# DragonflyteConnector.net
KiCad netlist of a schematic drawn in Altium Designer
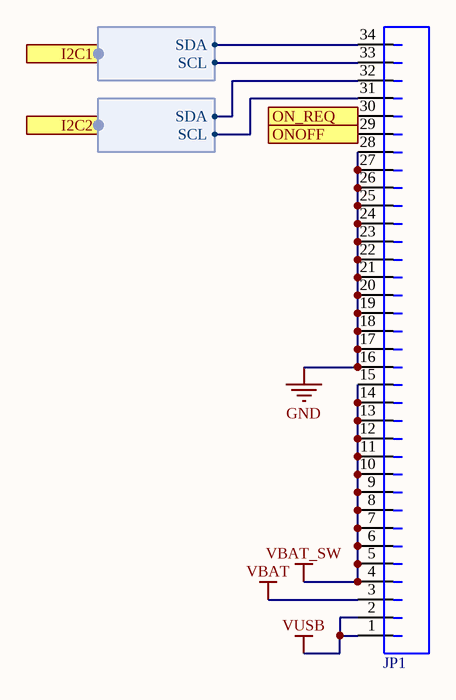
[diagram p0: DragonflyteConnector.SchDoc]

(export (version "E")
  (design (tool "Eeschema 10.0.6"))
  (components
    (comp (ref "JP1")
      (value "MOLEX_FFC-FPC_34")
      (footprint "MOLEX-FFC-FPC-0.5MM-34")
      (fields (field (name "MANUFACTURER") "Molex") (field (name "PARTNUMBER") "51296-3494"))
      (libsource (lib "Connectors") (part "MOLEX_FFC-FPC_34"))
    )
  )
  (nets
    (net (code "2") (name "/ONOFF") (class "Default")
      (node (ref "JP1") (pin "29") (pinfunction "29_29") (pintype "passive"))
    )
    (net (code "3") (name "/ON_REQ") (class "Default")
      (node (ref "JP1") (pin "30") (pinfunction "30_30") (pintype "passive"))
    )
    (net (code "5") (name "GND") (class "Default")
      (node (ref "JP1") (pin "16") (pinfunction "16_16") (pintype "passive"))
      (node (ref "JP1") (pin "17") (pinfunction "17_17") (pintype "passive"))
      (node (ref "JP1") (pin "18") (pinfunction "18_18") (pintype "passive"))
      (node (ref "JP1") (pin "19") (pinfunction "19_19") (pintype "passive"))
      (node (ref "JP1") (pin "20") (pinfunction "20_20") (pintype "passive"))
      (node (ref "JP1") (pin "21") (pinfunction "21_21") (pintype "passive"))
      (node (ref "JP1") (pin "22") (pinfunction "22_22") (pintype "passive"))
      (node (ref "JP1") (pin "23") (pinfunction "23_23") (pintype "passive"))
      (node (ref "JP1") (pin "24") (pinfunction "24_24") (pintype "passive"))
      (node (ref "JP1") (pin "25") (pinfunction "25_25") (pintype "passive"))
      (node (ref "JP1") (pin "26") (pinfunction "26_26") (pintype "passive"))
      (node (ref "JP1") (pin "27") (pinfunction "27_27") (pintype "passive"))
      (node (ref "JP1") (pin "28") (pinfunction "28_28") (pintype "passive"))
    )
    (net (code "6") (name "VBAT") (class "Default")
      (node (ref "JP1") (pin "3") (pinfunction "3_3") (pintype "passive"))
    )
    (net (code "7") (name "VBAT_SW") (class "Default")
      (node (ref "JP1") (pin "10") (pinfunction "10_10") (pintype "passive"))
      (node (ref "JP1") (pin "11") (pinfunction "11_11") (pintype "passive"))
      (node (ref "JP1") (pin "12") (pinfunction "12_12") (pintype "passive"))
      (node (ref "JP1") (pin "13") (pinfunction "13_13") (pintype "passive"))
      (node (ref "JP1") (pin "14") (pinfunction "14_14") (pintype "passive"))
      (node (ref "JP1") (pin "15") (pinfunction "15_15") (pintype "passive"))
      (node (ref "JP1") (pin "4") (pinfunction "4_4") (pintype "passive"))
      (node (ref "JP1") (pin "5") (pinfunction "5_5") (pintype "passive"))
      (node (ref "JP1") (pin "6") (pinfunction "6_6") (pintype "passive"))
      (node (ref "JP1") (pin "7") (pinfunction "7_7") (pintype "passive"))
      (node (ref "JP1") (pin "8") (pinfunction "8_8") (pintype "passive"))
      (node (ref "JP1") (pin "9") (pinfunction "9_9") (pintype "passive"))
    )
    (net (code "8") (name "VUSB") (class "Default")
      (node (ref "JP1") (pin "1") (pinfunction "1_1") (pintype "passive"))
      (node (ref "JP1") (pin "2") (pinfunction "2_2") (pintype "passive"))
    )
    (net (code "9") (name "unconnected-(JP1-Pad31)") (class "Default")
      (node (ref "JP1") (pin "31") (pinfunction "31_31") (pintype "passive"))
    )
    (net (code "10") (name "unconnected-(JP1-Pad32)") (class "Default")
      (node (ref "JP1") (pin "32") (pinfunction "32_32") (pintype "passive"))
    )
    (net (code "11") (name "unconnected-(JP1-Pad33)") (class "Default")
      (node (ref "JP1") (pin "33") (pinfunction "33_33") (pintype "passive"))
    )
    (net (code "12") (name "unconnected-(JP1-Pad34)") (class "Default")
      (node (ref "JP1") (pin "34") (pinfunction "34_34") (pintype "passive"))
    )
  )
)
